# ATMEGA2560-16AU.net
KiCad netlist of a schematic drawn in Altium Designer
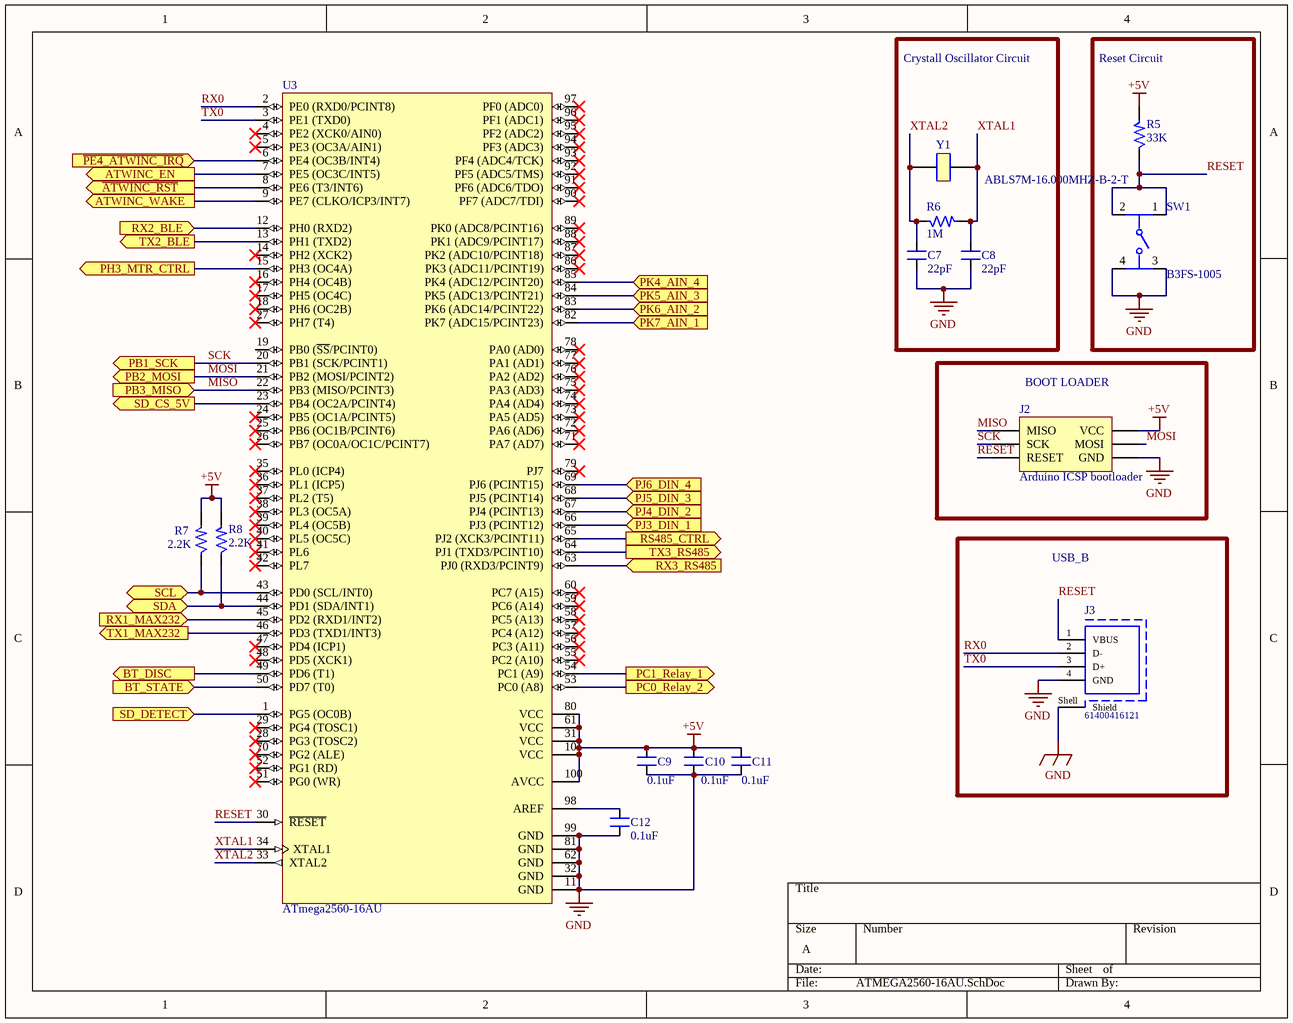
[diagram p0: ATMEGA2560-16AU.SchDoc]

(export (version "E")
  (design (tool "Eeschema 10.0.6"))
  (components
    (comp (ref "C7")
      (value "22pF")
      (footprint "CAP_0805")
      (description "22pF ±5% 50V Ceramic Capacitor C0G, NP0 0805 (2012 Metric)")
      (fields
        (field (name "MANUFACTURER") "Yageo")
        (field (name "MANUFACTURER PART NUMBER") "CC0805JRNPO9BN220")
      )
      (libsource (lib "ESTEEMPCBLIB") (part "CAP_22PF-50V-5%-0805"))
    )
    (comp (ref "C8")
      (value "22pF")
      (footprint "CAP_0805")
      (description "22pF ±5% 50V Ceramic Capacitor C0G, NP0 0805 (2012 Metric)")
      (fields
        (field (name "MANUFACTURER") "Yageo")
        (field (name "MANUFACTURER PART NUMBER") "CC0805JRNPO9BN220")
      )
      (libsource (lib "ESTEEMPCBLIB") (part "CAP_22PF-50V-5%-0805"))
    )
    (comp (ref "C9")
      (value "0.1uF")
      (footprint "CAP_0805")
      (description "0.1µF ±5% 50V Ceramic Capacitor X7R 0805 (2012 Metric)")
      (fields
        (field (name "MANUFACTURER") "AVX Corporation")
        (field (name "MANUFACTURER PART NUMBER") "08055C104JAT4A")
      )
      (libsource (lib "ESTEEMPCBLIB") (part "CAP_0.1uF-50V-5%-0805"))
    )
    (comp (ref "C10")
      (value "0.1uF")
      (footprint "CAP_0805")
      (description "0.1µF ±5% 50V Ceramic Capacitor X7R 0805 (2012 Metric)")
      (fields
        (field (name "MANUFACTURER") "AVX Corporation")
        (field (name "MANUFACTURER PART NUMBER") "08055C104JAT4A")
      )
      (libsource (lib "ESTEEMPCBLIB") (part "CAP_0.1uF-50V-5%-0805"))
    )
    (comp (ref "C11")
      (value "0.1uF")
      (footprint "CAP_0805")
      (description "0.1µF ±5% 50V Ceramic Capacitor X7R 0805 (2012 Metric)")
      (fields
        (field (name "MANUFACTURER") "AVX Corporation")
        (field (name "MANUFACTURER PART NUMBER") "08055C104JAT4A")
      )
      (libsource (lib "ESTEEMPCBLIB") (part "CAP_0.1uF-50V-5%-0805"))
    )
    (comp (ref "C12")
      (value "0.1uF")
      (footprint "CAP_0805")
      (description "0.1µF ±5% 50V Ceramic Capacitor X7R 0805 (2012 Metric)")
      (fields
        (field (name "MANUFACTURER") "AVX Corporation")
        (field (name "MANUFACTURER PART NUMBER") "08055C104JAT4A")
      )
      (libsource (lib "ESTEEMPCBLIB") (part "CAP_0.1uF-50V-5%-0805"))
    )
    (comp (ref "J2")
      (value "Arduino ICSP bootloader")
      (footprint "HDR2X3")
      (description "Header, 3-Pin, Dual row")
      (fields (field (name "PUBLISHER") "Altium Limited"))
      (libsource (lib "TAREKPCBLIB") (part "ICSP"))
    )
    (comp (ref "J3")
      (value "61400416121")
      (footprint "61400416121")
      (description "USB 2.0 Type B Receptacle WR-COM, Horizontal, THT, with Pads and Pegs")
      (fields (field (name "MANUFACTURER") "Wurth Elektronik") (field (name "PUBLISHER") "WurthElektronik"))
      (libsource (lib "TAREKPCBLIB") (part "CON_USB-2.0-B-TH"))
    )
    (comp (ref "R5")
      (value "33K")
      (footprint "RES_0805")
      (fields
        (field (name "MANUFACTURER") "Vishay BCcomponents")
        (field (name "MANUFACTURER PART NUMBER") "CRG0805F33K")
      )
      (libsource (lib "ESTEEMPCBLIB") (part "RES_33K-0.125W-1%-0805"))
    )
    (comp (ref "R6")
      (value "1M")
      (footprint "RES_0805")
      (description "1 MOhms ±1% 0.125W, 1/8W Chip Resistor 0805 (2012 Metric) Automotive AEC-Q200 Thick Film")
      (fields (field (name "MANUFACTURER") "Walsin") (field (name "MANUFACTURER PART NUMBER") "WR08X1004FTL"))
      (libsource (lib "ESTEEMPCBLIB") (part "RES_1M-0.125W-1%-0805"))
    )
    (comp (ref "R7")
      (value "2.2K")
      (footprint "RES_0805")
      (description "2.2 kOhms ±1% 0.125W, 1/8W Chip Resistor 0805 (2012 Metric) Thick Film")
      (fields
        (field (name "MANUFACTURER") "Stackpole Electronics")
        (field (name "MANUFACTURER PART NUMBER") "CRG0805F2K2")
      )
      (libsource (lib "ESTEEMPCBLIB") (part "RES_2.2K-0.125W-1%-0805"))
    )
    (comp (ref "R8")
      (value "2.2K")
      (footprint "RES_0805")
      (description "2.2 kOhms ±1% 0.125W, 1/8W Chip Resistor 0805 (2012 Metric) Thick Film")
      (fields
        (field (name "MANUFACTURER") "Stackpole Electronics")
        (field (name "MANUFACTURER PART NUMBER") "CRG0805F2K2")
      )
      (libsource (lib "ESTEEMPCBLIB") (part "RES_2.2K-0.125W-1%-0805"))
    )
    (comp (ref "SW1")
      (value "B3FS-1005")
      (footprint "FP-B3FS-1005-MFG")
      (description "SWITCH TACTILE SPST-NO 0.05A 24V")
      (libsource (lib "TAREKPCBLIB") (part "SWITCH TACTILE SPST"))
    )
    (comp (ref "U3")
      (value "ATmega2560-16AU")
      (footprint "100A_L")
      (libsource (lib "TAREKPCBLIB") (part "ATmega2560-16AU"))
    )
    (comp (ref "Y1")
      (value "ABLS7M-16.000MHZ-B-2-T")
      (footprint "XTAL_314_240X47_SMD")
      (description "16MHz ±20ppm Crystal 18pF 60 Ohms 2-SMD, Flat Lead")
      (fields (field (name "MANUFACTURER") "Abracon"))
      (libsource (lib "ESTEEMPCBLIB") (part "XTAL_16MHz-ABLS7M-16.000MHZ-B-2-T"))
    )
  )
  (nets
    (net (code "1") (name "+5V") (class "Default")
      (node (ref "C10") (pin "2") (pinfunction "2_2") (pintype "passive"))
      (node (ref "C11") (pin "2") (pinfunction "2_2") (pintype "passive"))
      (node (ref "C9") (pin "2") (pinfunction "2_2") (pintype "passive"))
      (node (ref "J2") (pin "2") (pinfunction "VCC_2") (pintype "passive"))
      (node (ref "R5") (pin "2") (pinfunction "2_2") (pintype "passive"))
      (node (ref "R7") (pin "2") (pinfunction "2_2") (pintype "passive"))
      (node (ref "R8") (pin "2") (pinfunction "2_2") (pintype "passive"))
      (node (ref "U3") (pin "10") (pinfunction "VCC_10") (pintype "power_in"))
      (node (ref "U3") (pin "100") (pinfunction "AVCC_100") (pintype "power_in"))
      (node (ref "U3") (pin "31") (pinfunction "VCC_31") (pintype "power_in"))
      (node (ref "U3") (pin "61") (pinfunction "VCC_61") (pintype "power_in"))
      (node (ref "U3") (pin "80") (pinfunction "VCC_80") (pintype "power_in"))
    )
    (net (code "2") (name "/ATWINC_EN") (class "Default")
      (node (ref "U3") (pin "7") (pinfunction "PE5_(OC3C/INT5)_7") (pintype "bidirectional"))
    )
    (net (code "3") (name "/ATWINC_RST") (class "Default")
      (node (ref "U3") (pin "8") (pinfunction "PE6_(T3/INT6)_8") (pintype "bidirectional"))
    )
    (net (code "4") (name "/ATWINC_WAKE") (class "Default")
      (node (ref "U3") (pin "9") (pinfunction "PE7_(CLKO/ICP3/INT7)_9") (pintype "bidirectional"))
    )
    (net (code "5") (name "/BT_DISC") (class "Default")
      (node (ref "U3") (pin "49") (pinfunction "PD6_(T1)_49") (pintype "bidirectional"))
    )
    (net (code "6") (name "/BT_STATE") (class "Default")
      (node (ref "U3") (pin "50") (pinfunction "PD7_(T0)_50") (pintype "bidirectional"))
    )
    (net (code "7") (name "/MISO") (class "Default")
      (node (ref "J2") (pin "1") (pinfunction "MISO_1") (pintype "passive"))
      (node (ref "U3") (pin "22") (pinfunction "PB3_(MISO/PCINT3)_22") (pintype "bidirectional"))
    )
    (net (code "8") (name "/MOSI") (class "Default")
      (node (ref "J2") (pin "4") (pinfunction "MOSI_4") (pintype "passive"))
      (node (ref "U3") (pin "21") (pinfunction "PB2_(MOSI/PCINT2)_21") (pintype "bidirectional"))
    )
    (net (code "9") (name "/PC0_Relay_2") (class "Default")
      (node (ref "U3") (pin "53") (pinfunction "PC0_(A8)_53") (pintype "bidirectional"))
    )
    (net (code "10") (name "/PC1_Relay_1") (class "Default")
      (node (ref "U3") (pin "54") (pinfunction "PC1_(A9)_54") (pintype "bidirectional"))
    )
    (net (code "11") (name "/PE4_ATWINC_IRQ") (class "Default")
      (node (ref "U3") (pin "6") (pinfunction "PE4_(OC3B/INT4)_6") (pintype "bidirectional"))
    )
    (net (code "12") (name "/PH3_MTR_CTRL") (class "Default")
      (node (ref "U3") (pin "15") (pinfunction "PH3_(OC4A)_15") (pintype "bidirectional"))
    )
    (net (code "13") (name "/PJ3_DIN_1") (class "Default")
      (node (ref "U3") (pin "66") (pinfunction "PJ3_(PCINT12)_66") (pintype "bidirectional"))
    )
    (net (code "14") (name "/PJ4_DIN_2") (class "Default")
      (node (ref "U3") (pin "67") (pinfunction "PJ4_(PCINT13)_67") (pintype "bidirectional"))
    )
    (net (code "15") (name "/PJ5_DIN_3") (class "Default")
      (node (ref "U3") (pin "68") (pinfunction "PJ5_(PCINT14)_68") (pintype "bidirectional"))
    )
    (net (code "16") (name "/PJ6_DIN_4") (class "Default")
      (node (ref "U3") (pin "69") (pinfunction "PJ6_(PCINT15)_69") (pintype "bidirectional"))
    )
    (net (code "17") (name "/PK4_AIN_4") (class "Default")
      (node (ref "U3") (pin "85") (pinfunction "PK4_(ADC12/PCINT20)_85") (pintype "bidirectional"))
    )
    (net (code "18") (name "/PK5_AIN_3") (class "Default")
      (node (ref "U3") (pin "84") (pinfunction "PK5_(ADC13/PCINT21)_84") (pintype "bidirectional"))
    )
    (net (code "19") (name "/PK6_AIN_2") (class "Default")
      (node (ref "U3") (pin "83") (pinfunction "PK6_(ADC14/PCINT22)_83") (pintype "bidirectional"))
    )
    (net (code "20") (name "/PK7_AIN_1") (class "Default")
      (node (ref "U3") (pin "82") (pinfunction "PK7_(ADC15/PCINT23)_82") (pintype "bidirectional"))
    )
    (net (code "21") (name "/RESET") (class "Default")
      (node (ref "J2") (pin "5") (pinfunction "RESET_5") (pintype "passive"))
      (node (ref "J3") (pin "1") (pinfunction "VBUS_1") (pintype "passive"))
      (node (ref "R5") (pin "1") (pinfunction "1_1") (pintype "passive"))
      (node (ref "SW1") (pin "1") (pinfunction "1_1") (pintype "passive"))
      (node (ref "SW1") (pin "2") (pinfunction "2_2") (pintype "passive"))
      (node (ref "U3") (pin "30") (pinfunction "~{RESET}_30") (pintype "input"))
    )
    (net (code "22") (name "/RS485_CTRL") (class "Default")
      (node (ref "U3") (pin "65") (pinfunction "PJ2_(XCK3/PCINT11)_65") (pintype "bidirectional"))
    )
    (net (code "23") (name "/RX0") (class "Default")
      (node (ref "J3") (pin "2") (pinfunction "D-_2") (pintype "passive"))
      (node (ref "U3") (pin "2") (pinfunction "PE0_(RXD0/PCINT8)_2") (pintype "bidirectional"))
    )
    (net (code "24") (name "/RX1_MAX232") (class "Default")
      (node (ref "U3") (pin "45") (pinfunction "PD2_(RXD1/INT2)_45") (pintype "bidirectional"))
    )
    (net (code "25") (name "/RX2_BLE") (class "Default")
      (node (ref "U3") (pin "12") (pinfunction "PH0_(RXD2)_12") (pintype "bidirectional"))
    )
    (net (code "26") (name "/RX3_RS485") (class "Default")
      (node (ref "U3") (pin "63") (pinfunction "PJ0_(RXD3/PCINT9)_63") (pintype "bidirectional"))
    )
    (net (code "27") (name "/SCK") (class "Default")
      (node (ref "J2") (pin "3") (pinfunction "SCK_3") (pintype "passive"))
      (node (ref "U3") (pin "20") (pinfunction "PB1_(SCK/PCINT1)_20") (pintype "bidirectional"))
    )
    (net (code "28") (name "/SCL") (class "Default")
      (node (ref "R7") (pin "1") (pinfunction "1_1") (pintype "passive"))
      (node (ref "U3") (pin "43") (pinfunction "PD0_(SCL/INT0)_43") (pintype "bidirectional"))
    )
    (net (code "29") (name "/SDA") (class "Default")
      (node (ref "R8") (pin "1") (pinfunction "1_1") (pintype "passive"))
      (node (ref "U3") (pin "44") (pinfunction "PD1_(SDA/INT1)_44") (pintype "bidirectional"))
    )
    (net (code "30") (name "/SD_CS_5V") (class "Default")
      (node (ref "U3") (pin "23") (pinfunction "PB4_(OC2A/PCINT4)_23") (pintype "bidirectional"))
    )
    (net (code "31") (name "/SD_DETECT") (class "Default")
      (node (ref "U3") (pin "1") (pinfunction "PG5_(OC0B)_1") (pintype "bidirectional"))
    )
    (net (code "32") (name "/TX0") (class "Default")
      (node (ref "J3") (pin "3") (pinfunction "D+_3") (pintype "passive"))
      (node (ref "U3") (pin "3") (pinfunction "PE1_(TXD0)_3") (pintype "bidirectional"))
    )
    (net (code "33") (name "/TX1_MAX232") (class "Default")
      (node (ref "U3") (pin "46") (pinfunction "PD3_(TXD1/INT3)_46") (pintype "bidirectional"))
    )
    (net (code "34") (name "/TX2_BLE") (class "Default")
      (node (ref "U3") (pin "13") (pinfunction "PH1_(TXD2)_13") (pintype "bidirectional"))
    )
    (net (code "35") (name "/TX3_RS485") (class "Default")
      (node (ref "U3") (pin "64") (pinfunction "PJ1_(TXD3/PCINT10)_64") (pintype "bidirectional"))
    )
    (net (code "36") (name "/XTAL1") (class "Default")
      (node (ref "C8") (pin "2") (pinfunction "2_2") (pintype "passive"))
      (node (ref "R6") (pin "2") (pinfunction "2_2") (pintype "passive"))
      (node (ref "U3") (pin "34") (pinfunction "XTAL1_34") (pintype "input"))
      (node (ref "Y1") (pin "2") (pinfunction "2_2") (pintype "passive"))
    )
    (net (code "37") (name "/XTAL2") (class "Default")
      (node (ref "C7") (pin "2") (pinfunction "2_2") (pintype "passive"))
      (node (ref "R6") (pin "1") (pinfunction "1_1") (pintype "passive"))
      (node (ref "U3") (pin "33") (pinfunction "XTAL2_33") (pintype "output"))
      (node (ref "Y1") (pin "1") (pinfunction "1_1") (pintype "passive"))
    )
    (net (code "38") (name "GND") (class "Default")
      (node (ref "C10") (pin "1") (pinfunction "1_1") (pintype "passive"))
      (node (ref "C11") (pin "1") (pinfunction "1_1") (pintype "passive"))
      (node (ref "C12") (pin "1") (pinfunction "1_1") (pintype "passive"))
      (node (ref "C7") (pin "1") (pinfunction "1_1") (pintype "passive"))
      (node (ref "C8") (pin "1") (pinfunction "1_1") (pintype "passive"))
      (node (ref "C9") (pin "1") (pinfunction "1_1") (pintype "passive"))
      (node (ref "J2") (pin "6") (pinfunction "GND_6") (pintype "passive"))
      (node (ref "J3") (pin "4") (pinfunction "GND_4") (pintype "passive"))
      (node (ref "J3") (pin "Shell") (pinfunction "Shield_Shell") (pintype "passive"))
      (node (ref "SW1") (pin "3") (pinfunction "3_3") (pintype "passive"))
      (node (ref "SW1") (pin "4") (pinfunction "4_4") (pintype "passive"))
      (node (ref "U3") (pin "11") (pinfunction "GND_11") (pintype "power_in"))
      (node (ref "U3") (pin "32") (pinfunction "GND_32") (pintype "power_in"))
      (node (ref "U3") (pin "62") (pinfunction "GND_62") (pintype "power_in"))
      (node (ref "U3") (pin "81") (pinfunction "GND_81") (pintype "power_in"))
      (node (ref "U3") (pin "99") (pinfunction "GND_99") (pintype "power_in"))
    )
    (net (code "39") (name "Net-(U3-AREF)") (class "Default")
      (node (ref "C12") (pin "2") (pinfunction "2_2") (pintype "passive"))
      (node (ref "U3") (pin "98") (pinfunction "AREF_98") (pintype "power_in"))
    )
    (net (code "40") (name "unconnected-(U3-PA0_(AD0)-Pad78)") (class "Default")
      (node (ref "U3") (pin "78") (pinfunction "PA0_(AD0)_78") (pintype "bidirectional+no_connect"))
    )
    (net (code "41") (name "unconnected-(U3-PA1_(AD1)-Pad77)") (class "Default")
      (node (ref "U3") (pin "77") (pinfunction "PA1_(AD1)_77") (pintype "bidirectional+no_connect"))
    )
    (net (code "42") (name "unconnected-(U3-PA2_(AD2)-Pad76)") (class "Default")
      (node (ref "U3") (pin "76") (pinfunction "PA2_(AD2)_76") (pintype "bidirectional+no_connect"))
    )
    (net (code "43") (name "unconnected-(U3-PA3_(AD3)-Pad75)") (class "Default")
      (node (ref "U3") (pin "75") (pinfunction "PA3_(AD3)_75") (pintype "bidirectional+no_connect"))
    )
    (net (code "44") (name "unconnected-(U3-PA4_(AD4)-Pad74)") (class "Default")
      (node (ref "U3") (pin "74") (pinfunction "PA4_(AD4)_74") (pintype "bidirectional+no_connect"))
    )
    (net (code "45") (name "unconnected-(U3-PA5_(AD5)-Pad73)") (class "Default")
      (node (ref "U3") (pin "73") (pinfunction "PA5_(AD5)_73") (pintype "bidirectional+no_connect"))
    )
    (net (code "46") (name "unconnected-(U3-PA6_(AD6)-Pad72)") (class "Default")
      (node (ref "U3") (pin "72") (pinfunction "PA6_(AD6)_72") (pintype "bidirectional+no_connect"))
    )
    (net (code "47") (name "unconnected-(U3-PA7_(AD7)-Pad71)") (class "Default")
      (node (ref "U3") (pin "71") (pinfunction "PA7_(AD7)_71") (pintype "bidirectional+no_connect"))
    )
    (net (code "48") (name "unconnected-(U3-PB0_(~{SS}{slash}PCINT0)-Pad19)") (class "Default")
      (node (ref "U3") (pin "19") (pinfunction "PB0_(~{SS}/PCINT0)_19") (pintype "bidirectional"))
    )
    (net (code "49") (name "unconnected-(U3-PB5_(OC1A{slash}PCINT5)-Pad24)") (class "Default")
      (node (ref "U3") (pin "24") (pinfunction "PB5_(OC1A/PCINT5)_24") (pintype "bidirectional+no_connect"))
    )
    (net (code "50") (name "unconnected-(U3-PB6_(OC1B{slash}PCINT6)-Pad25)") (class "Default")
      (node (ref "U3") (pin "25") (pinfunction "PB6_(OC1B/PCINT6)_25") (pintype "bidirectional+no_connect"))
    )
    (net (code "51") (name "unconnected-(U3-PB7_(OC0A{slash}OC1C{slash}PCINT7)-Pad26)") (class "Default")
      (node (ref "U3") (pin "26") (pinfunction "PB7_(OC0A/OC1C/PCINT7)_26") (pintype "bidirectional+no_connect"))
    )
    (net (code "52") (name "unconnected-(U3-PC2_(A10)-Pad55)") (class "Default")
      (node (ref "U3") (pin "55") (pinfunction "PC2_(A10)_55") (pintype "bidirectional+no_connect"))
    )
    (net (code "53") (name "unconnected-(U3-PC3_(A11)-Pad56)") (class "Default")
      (node (ref "U3") (pin "56") (pinfunction "PC3_(A11)_56") (pintype "bidirectional+no_connect"))
    )
    (net (code "54") (name "unconnected-(U3-PC4_(A12)-Pad57)") (class "Default")
      (node (ref "U3") (pin "57") (pinfunction "PC4_(A12)_57") (pintype "bidirectional+no_connect"))
    )
    (net (code "55") (name "unconnected-(U3-PC5_(A13)-Pad58)") (class "Default")
      (node (ref "U3") (pin "58") (pinfunction "PC5_(A13)_58") (pintype "bidirectional+no_connect"))
    )
    (net (code "56") (name "unconnected-(U3-PC6_(A14)-Pad59)") (class "Default")
      (node (ref "U3") (pin "59") (pinfunction "PC6_(A14)_59") (pintype "bidirectional+no_connect"))
    )
    (net (code "57") (name "unconnected-(U3-PC7_(A15)-Pad60)") (class "Default")
      (node (ref "U3") (pin "60") (pinfunction "PC7_(A15)_60") (pintype "bidirectional+no_connect"))
    )
    (net (code "58") (name "unconnected-(U3-PD4_(ICP1)-Pad47)") (class "Default")
      (node (ref "U3") (pin "47") (pinfunction "PD4_(ICP1)_47") (pintype "bidirectional+no_connect"))
    )
    (net (code "59") (name "unconnected-(U3-PD5_(XCK1)-Pad48)") (class "Default")
      (node (ref "U3") (pin "48") (pinfunction "PD5_(XCK1)_48") (pintype "bidirectional+no_connect"))
    )
    (net (code "60") (name "unconnected-(U3-PE2_(XCK0{slash}AIN0)-Pad4)") (class "Default")
      (node (ref "U3") (pin "4") (pinfunction "PE2_(XCK0/AIN0)_4") (pintype "bidirectional+no_connect"))
    )
    (net (code "61") (name "unconnected-(U3-PE3_(OC3A{slash}AIN1)-Pad5)") (class "Default")
      (node (ref "U3") (pin "5") (pinfunction "PE3_(OC3A/AIN1)_5") (pintype "bidirectional+no_connect"))
    )
    (net (code "62") (name "unconnected-(U3-PF0_(ADC0)-Pad97)") (class "Default")
      (node (ref "U3") (pin "97") (pinfunction "PF0_(ADC0)_97") (pintype "bidirectional+no_connect"))
    )
    (net (code "63") (name "unconnected-(U3-PF1_(ADC1)-Pad96)") (class "Default")
      (node (ref "U3") (pin "96") (pinfunction "PF1_(ADC1)_96") (pintype "bidirectional+no_connect"))
    )
    (net (code "64") (name "unconnected-(U3-PF2_(ADC2)-Pad95)") (class "Default")
      (node (ref "U3") (pin "95") (pinfunction "PF2_(ADC2)_95") (pintype "bidirectional+no_connect"))
    )
    (net (code "65") (name "unconnected-(U3-PF3_(ADC3)-Pad94)") (class "Default")
      (node (ref "U3") (pin "94") (pinfunction "PF3_(ADC3)_94") (pintype "bidirectional+no_connect"))
    )
    (net (code "66") (name "unconnected-(U3-PF4_(ADC4{slash}TCK)-Pad93)") (class "Default")
      (node (ref "U3") (pin "93") (pinfunction "PF4_(ADC4/TCK)_93") (pintype "bidirectional+no_connect"))
    )
    (net (code "67") (name "unconnected-(U3-PF5_(ADC5{slash}TMS)-Pad92)") (class "Default")
      (node (ref "U3") (pin "92") (pinfunction "PF5_(ADC5/TMS)_92") (pintype "bidirectional+no_connect"))
    )
    (net (code "68") (name "unconnected-(U3-PF6_(ADC6{slash}TDO)-Pad91)") (class "Default")
      (node (ref "U3") (pin "91") (pinfunction "PF6_(ADC6/TDO)_91") (pintype "bidirectional+no_connect"))
    )
    (net (code "69") (name "unconnected-(U3-PF7_(ADC7{slash}TDI)-Pad90)") (class "Default")
      (node (ref "U3") (pin "90") (pinfunction "PF7_(ADC7/TDI)_90") (pintype "bidirectional+no_connect"))
    )
    (net (code "70") (name "unconnected-(U3-PG0_(WR)-Pad51)") (class "Default")
      (node (ref "U3") (pin "51") (pinfunction "PG0_(WR)_51") (pintype "bidirectional+no_connect"))
    )
    (net (code "71") (name "unconnected-(U3-PG1_(RD)-Pad52)") (class "Default")
      (node (ref "U3") (pin "52") (pinfunction "PG1_(RD)_52") (pintype "bidirectional+no_connect"))
    )
    (net (code "72") (name "unconnected-(U3-PG2_(ALE)-Pad70)") (class "Default")
      (node (ref "U3") (pin "70") (pinfunction "PG2_(ALE)_70") (pintype "bidirectional+no_connect"))
    )
    (net (code "73") (name "unconnected-(U3-PG3_(TOSC2)-Pad28)") (class "Default")
      (node (ref "U3") (pin "28") (pinfunction "PG3_(TOSC2)_28") (pintype "bidirectional+no_connect"))
    )
    (net (code "74") (name "unconnected-(U3-PG4_(TOSC1)-Pad29)") (class "Default")
      (node (ref "U3") (pin "29") (pinfunction "PG4_(TOSC1)_29") (pintype "bidirectional+no_connect"))
    )
    (net (code "75") (name "unconnected-(U3-PH2_(XCK2)-Pad14)") (class "Default")
      (node (ref "U3") (pin "14") (pinfunction "PH2_(XCK2)_14") (pintype "bidirectional+no_connect"))
    )
    (net (code "76") (name "unconnected-(U3-PH4_(OC4B)-Pad16)") (class "Default")
      (node (ref "U3") (pin "16") (pinfunction "PH4_(OC4B)_16") (pintype "bidirectional+no_connect"))
    )
    (net (code "77") (name "unconnected-(U3-PH5_(OC4C)-Pad17)") (class "Default")
      (node (ref "U3") (pin "17") (pinfunction "PH5_(OC4C)_17") (pintype "bidirectional+no_connect"))
    )
    (net (code "78") (name "unconnected-(U3-PH6_(OC2B)-Pad18)") (class "Default")
      (node (ref "U3") (pin "18") (pinfunction "PH6_(OC2B)_18") (pintype "bidirectional+no_connect"))
    )
    (net (code "79") (name "unconnected-(U3-PH7_(T4)-Pad27)") (class "Default")
      (node (ref "U3") (pin "27") (pinfunction "PH7_(T4)_27") (pintype "bidirectional+no_connect"))
    )
    (net (code "80") (name "unconnected-(U3-PJ7-Pad79)") (class "Default")
      (node (ref "U3") (pin "79") (pinfunction "PJ7_79") (pintype "bidirectional+no_connect"))
    )
    (net (code "81") (name "unconnected-(U3-PK0_(ADC8{slash}PCINT16)-Pad89)") (class "Default")
      (node (ref "U3") (pin "89") (pinfunction "PK0_(ADC8/PCINT16)_89") (pintype "bidirectional+no_connect"))
    )
    (net (code "82") (name "unconnected-(U3-PK1_(ADC9{slash}PCINT17)-Pad88)") (class "Default")
      (node (ref "U3") (pin "88") (pinfunction "PK1_(ADC9/PCINT17)_88") (pintype "bidirectional+no_connect"))
    )
    (net (code "83") (name "unconnected-(U3-PK2_(ADC10{slash}PCINT18)-Pad87)") (class "Default")
      (node (ref "U3") (pin "87") (pinfunction "PK2_(ADC10/PCINT18)_87") (pintype "bidirectional+no_connect"))
    )
    (net (code "84") (name "unconnected-(U3-PK3_(ADC11{slash}PCINT19)-Pad86)") (class "Default")
      (node (ref "U3") (pin "86") (pinfunction "PK3_(ADC11/PCINT19)_86") (pintype "bidirectional+no_connect"))
    )
    (net (code "85") (name "unconnected-(U3-PL0_(ICP4)-Pad35)") (class "Default")
      (node (ref "U3") (pin "35") (pinfunction "PL0_(ICP4)_35") (pintype "bidirectional+no_connect"))
    )
    (net (code "86") (name "unconnected-(U3-PL1_(ICP5)-Pad36)") (class "Default")
      (node (ref "U3") (pin "36") (pinfunction "PL1_(ICP5)_36") (pintype "bidirectional+no_connect"))
    )
    (net (code "87") (name "unconnected-(U3-PL2_(T5)-Pad37)") (class "Default")
      (node (ref "U3") (pin "37") (pinfunction "PL2_(T5)_37") (pintype "bidirectional+no_connect"))
    )
    (net (code "88") (name "unconnected-(U3-PL3_(OC5A)-Pad38)") (class "Default")
      (node (ref "U3") (pin "38") (pinfunction "PL3_(OC5A)_38") (pintype "bidirectional+no_connect"))
    )
    (net (code "89") (name "unconnected-(U3-PL4_(OC5B)-Pad39)") (class "Default")
      (node (ref "U3") (pin "39") (pinfunction "PL4_(OC5B)_39") (pintype "bidirectional+no_connect"))
    )
    (net (code "90") (name "unconnected-(U3-PL5_(OC5C)-Pad40)") (class "Default")
      (node (ref "U3") (pin "40") (pinfunction "PL5_(OC5C)_40") (pintype "bidirectional+no_connect"))
    )
    (net (code "91") (name "unconnected-(U3-PL6-Pad41)") (class "Default")
      (node (ref "U3") (pin "41") (pinfunction "PL6_41") (pintype "bidirectional+no_connect"))
    )
    (net (code "92") (name "unconnected-(U3-PL7-Pad42)") (class "Default")
      (node (ref "U3") (pin "42") (pinfunction "PL7_42") (pintype "bidirectional+no_connect"))
    )
  )
)
